# Camera_Board.net
KiCad netlist of a schematic drawn in Altium Designer
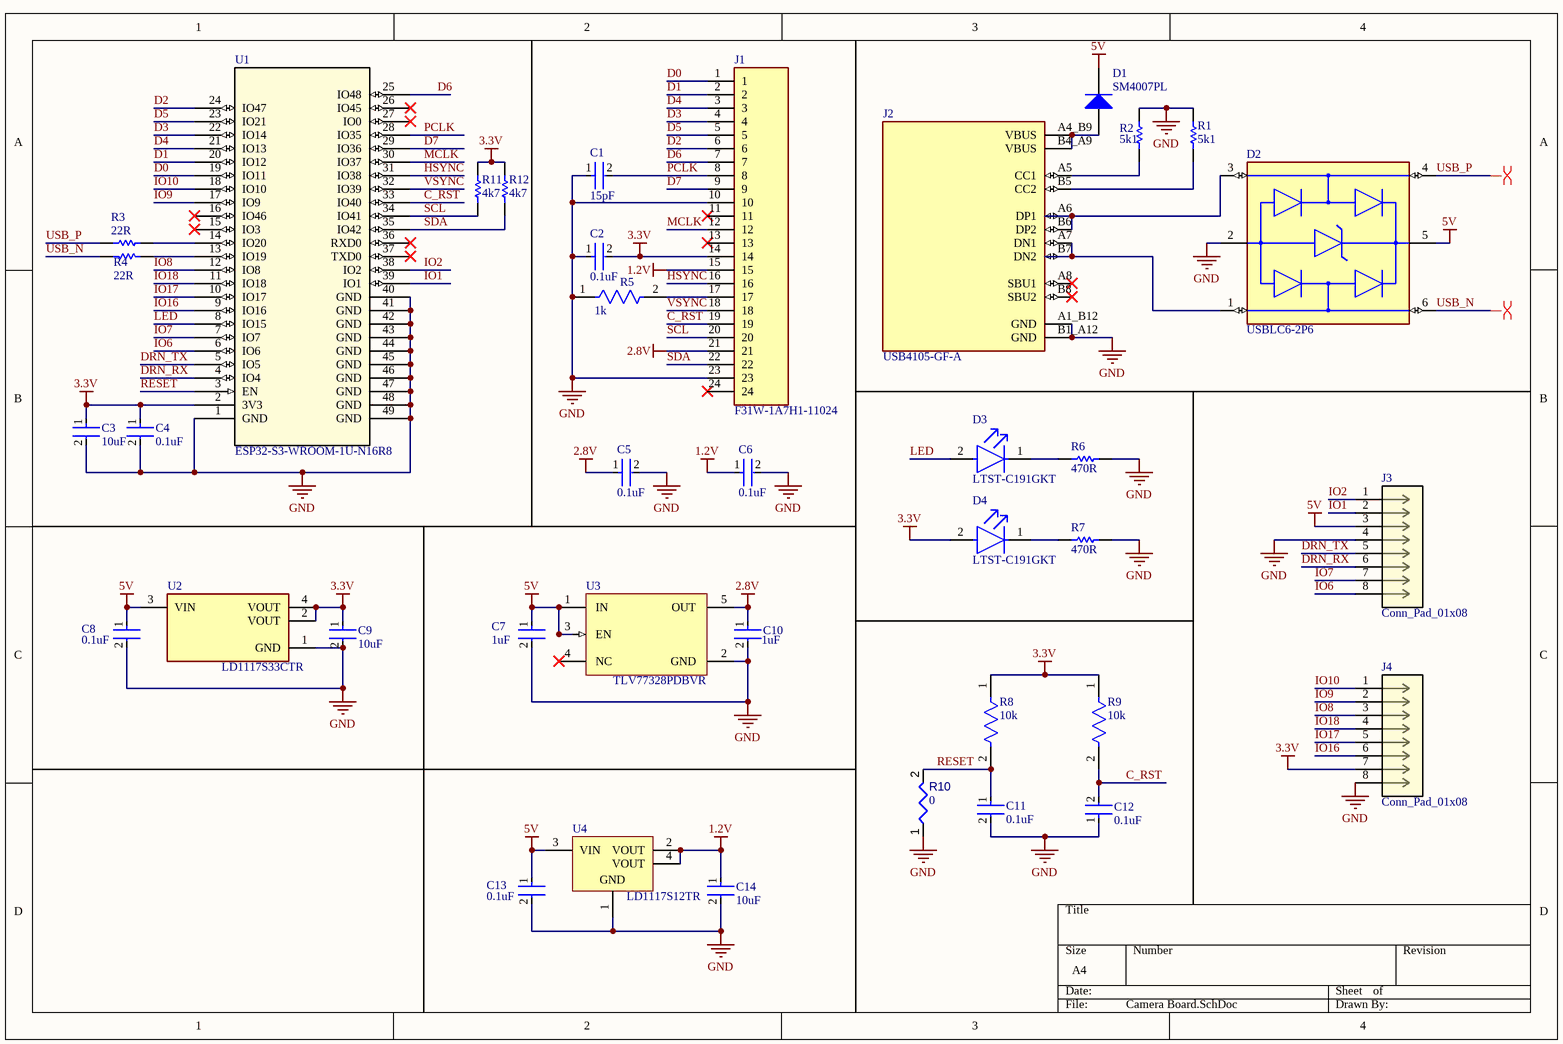
[diagram p0: Camera Board.SchDoc]

(export (version "E")
  (design (tool "Eeschema 10.0.6"))
  (components
    (comp (ref "C1")
      (value "15pF")
      (footprint "FP-CC0402-0_55-IPC_B")
      (description "CAP CER 15PF 50V C0G/NPO 0402")
      (fields (field (name "VOLTAGE") "50V") (field (name "TOLERANCE") "5%"))
      (libsource (lib "Altium Content Vault") (part "b4654b650e69147ec39a6b967a45e02"))
    )
    (comp (ref "C2")
      (value "0.1uF")
      (footprint "FP-GRM155-0_05-IPC_B")
      (description "Chip Multilayer Ceramic Capacitors for General Purpose, 0402, 0.10uF, X7R, 15%, 10%, 50V")
      (fields (field (name "VOLTAGE") "50V") (field (name "TOLERANCE") "10%"))
      (libsource (lib "Altium Content Vault") (part "02cd4be3c70576c341d710602a673aa"))
    )
    (comp (ref "C3")
      (value "10uF")
      (footprint "FP-GRM18-0_15-MFG")
      (description "CAP CER 10UF 10V X5R 0603")
      (fields
        (field (name "OCTOPART") "https://octopart.com/grm188r61a106ke69d-murata-22851381")
        (field (name "MANUFACTURER PART NUMBER") "GRM188R61A106KE69D")
      )
      (libsource (lib "Altium Content Vault") (part "11868f565c42a9108669ba33697ecf6"))
    )
    (comp (ref "C4")
      (value "0.1uF")
      (footprint "FP-CC0603-DA-MFG")
      (description "CAP CER 0.1UF 50V X7R 0603")
      (fields (field (name "MANUFACTURER") "YAGEO") (field (name "VOLTAGE") "50 V"))
      (libsource (lib "Altium Content Vault") (part "11868f565c42a9108669ba33697ecf6"))
    )
    (comp (ref "C5")
      (value "0.1uF")
      (footprint "FP-GRM155-0_05-IPC_B")
      (description "Chip Multilayer Ceramic Capacitors for General Purpose, 0402, 0.10uF, X7R, 15%, 10%, 50V")
      (fields (field (name "VOLTAGE") "50V") (field (name "TOLERANCE") "10%"))
      (libsource (lib "Altium Content Vault") (part "02cd4be3c70576c341d710602a673aa"))
    )
    (comp (ref "C6")
      (value "0.1uF")
      (footprint "FP-GRM155-0_05-IPC_B")
      (description "Chip Multilayer Ceramic Capacitors for General Purpose, 0402, 0.10uF, X7R, 15%, 10%, 50V")
      (fields (field (name "VOLTAGE") "50V") (field (name "TOLERANCE") "10%"))
      (libsource (lib "Altium Content Vault") (part "02cd4be3c70576c341d710602a673aa"))
    )
    (comp (ref "C7")
      (value "1uF")
      (footprint "FP-CC0603-DB-MFG")
      (description "CAP CER 1UF 50V X7R 0603")
      (fields (field (name "TOLERANCE") "10%"))
      (libsource (lib "Altium Content Vault") (part "11868f565c42a9108669ba33697ecf6"))
    )
    (comp (ref "C8")
      (value "0.1uF")
      (footprint "FP-CC0603-DA-MFG")
      (description "CAP CER 0.1UF 50V X7R 0603")
      (fields (field (name "MANUFACTURER") "YAGEO") (field (name "VOLTAGE") "50 V"))
      (libsource (lib "Altium Content Vault") (part "11868f565c42a9108669ba33697ecf6"))
    )
    (comp (ref "C9")
      (value "10uF")
      (footprint "FP-GRM18-0_15-MFG")
      (description "CAP CER 10UF 10V X5R 0603")
      (fields
        (field (name "OCTOPART") "https://octopart.com/grm188r61a106ke69d-murata-22851381")
        (field (name "MANUFACTURER PART NUMBER") "GRM188R61A106KE69D")
      )
      (libsource (lib "Altium Content Vault") (part "11868f565c42a9108669ba33697ecf6"))
    )
    (comp (ref "C10")
      (value "1uF")
      (footprint "FP-CC0603-DB-MFG")
      (description "CAP CER 1UF 50V X7R 0603")
      (fields (field (name "TOLERANCE") "10%"))
      (libsource (lib "Altium Content Vault") (part "11868f565c42a9108669ba33697ecf6"))
    )
    (comp (ref "C11")
      (value "0.1uF")
      (footprint "FP-CC0603-DA-MFG")
      (description "CAP CER 0.1UF 50V X7R 0603")
      (fields (field (name "MANUFACTURER") "YAGEO") (field (name "VOLTAGE") "50 V"))
      (libsource (lib "Altium Content Vault") (part "11868f565c42a9108669ba33697ecf6"))
    )
    (comp (ref "C12")
      (value "0.1uF")
      (footprint "FP-GRM155-0_05-IPC_B")
      (description "Chip Multilayer Ceramic Capacitors for General Purpose, 0402, 0.10uF, X7R, 15%, 10%, 50V")
      (fields (field (name "VOLTAGE") "50V") (field (name "TOLERANCE") "10%"))
      (libsource (lib "Altium Content Vault") (part "02cd4be3c70576c341d710602a673aa"))
    )
    (comp (ref "C13")
      (value "0.1uF")
      (footprint "FP-CC0603-DA-MFG")
      (description "CAP CER 0.1UF 50V X7R 0603")
      (fields (field (name "MANUFACTURER") "YAGEO") (field (name "VOLTAGE") "50 V"))
      (libsource (lib "Altium Content Vault") (part "11868f565c42a9108669ba33697ecf6"))
    )
    (comp (ref "C14")
      (value "10uF")
      (footprint "FP-GRM18-0_15-MFG")
      (description "CAP CER 10UF 10V X5R 0603")
      (fields
        (field (name "OCTOPART") "https://octopart.com/grm188r61a106ke69d-murata-22851381")
        (field (name "MANUFACTURER PART NUMBER") "GRM188R61A106KE69D")
      )
      (libsource (lib "Altium Content Vault") (part "11868f565c42a9108669ba33697ecf6"))
    )
    (comp (ref "D1")
      (value "SM4007PL")
      (footprint "MCC-SOD-123FL_V")
      (description "Silion Rectifier, 1 A, 1000 V, -65 to 175 degC, 2-Pin SMD, RoHS, Tape and Reel")
      (fields (field (name "MANUFACTURER") "Micro Commercial Components"))
      (libsource (lib "Altium Content Vault") (part "D-AK-2"))
    )
    (comp (ref "D2")
      (value "USBLC6-2P6")
      (footprint "FP-SOT-666-MFG")
      (description "TVS DIODE 5.25V 17V SOT666")
      (libsource (lib "Altium Content Vault") (part "c871e55f7e3243d341edbd671b98d92"))
    )
    (comp (ref "D3")
      (value "LTST-C191GKT")
      (footprint "FP-LTST-C191GKT-MFG")
      (description "LED GREEN CLEAR CHIP SMD")
      (libsource (lib "Altium Content Vault") (part "8706943c75ba83719d021d2fdc84c58"))
    )
    (comp (ref "D4")
      (value "LTST-C191GKT")
      (footprint "FP-LTST-C191GKT-MFG")
      (description "LED GREEN CLEAR CHIP SMD")
      (libsource (lib "Altium Content Vault") (part "8706943c75ba83719d021d2fdc84c58"))
    )
    (comp (ref "J1")
      (value "F31W-1A7H1-11024")
      (footprint "AMPHENOL_F31W-1A7H1-11024")
      (fields (field (name "MF") "Amphenol ICC / Aorora"))
      (libsource (lib "Adam Turaj") (part "F31W-1A7H1-11024"))
    )
    (comp (ref "J2")
      (value "USB4105-GF-A")
      (footprint "GCT_USB4105-GF-A")
      (fields (field (name "MF") "{'manufacturer': u'GCT'}"))
      (libsource (lib "Adam Turaj") (part "USB4105-GF-A"))
    )
    (comp (ref "J3")
      (value "Conn_Pad_01x08")
      (footprint "CONN_SM08B-GHS-TB_JST")
      (description "Description")
      (fields (field (name "COPYRIGHT") "Copyright (C) 2026 Ultra Librarian. All rights reserved."))
      (libsource (lib "Adam Turaj") (part "SM08B-GHS-TB"))
    )
    (comp (ref "J4")
      (value "Conn_Pad_01x08")
      (footprint "CONN_SM08B-GHS-TB_JST")
      (description "Description")
      (fields (field (name "COPYRIGHT") "Copyright (C) 2026 Ultra Librarian. All rights reserved."))
      (libsource (lib "Adam Turaj") (part "SM08B-GHS-TB"))
    )
    (comp (ref "R1")
      (value "5k1")
      (footprint "RESC1608X55X25ML10T15")
      (fields (field (name "MANUFACTURER") "Yageo") (field (name "PART NUMBER") "RC0603FR-075K1L"))
      (libsource (lib "Altium Content Vault") (part "RES"))
    )
    (comp (ref "R2")
      (value "5k1")
      (footprint "RESC1608X55X25ML10T15")
      (fields (field (name "MANUFACTURER") "Yageo") (field (name "PART NUMBER") "RC0603FR-075K1L"))
      (libsource (lib "Altium Content Vault") (part "RES"))
    )
    (comp (ref "R3")
      (value "22R")
      (footprint "RESC1608X55X25NL10T15")
      (description "Chip Resistor, 22 Ohm, +/- 1%, 0.1 W, -55 to 155 degC, 0603 (1608 Metric), RoHS, Tape and Reel")
      (libsource (lib "Altium Content Vault") (part "RES-2"))
    )
    (comp (ref "R4")
      (value "22R")
      (footprint "RESC1608X55X25NL10T15")
      (description "Chip Resistor, 22 Ohm, +/- 1%, 0.1 W, -55 to 155 degC, 0603 (1608 Metric), RoHS, Tape and Reel")
      (libsource (lib "Altium Content Vault") (part "RES-2"))
    )
    (comp (ref "R5")
      (value "1k")
      (footprint "FP-RC0603-0_55-IPC_C")
      (description "RES 1K OHM 1% 1/10W 0603")
      (fields (field (name "TOLERANCE") "1%"))
      (libsource (lib "Altium Content Vault") (part "1029c3af85768c4190bb7ad29bc67b5"))
    )
    (comp (ref "R6")
      (value "470R")
      (footprint "RESC1608X55X25LL10T15")
      (libsource (lib "Altium Content Vault") (part "RES-2"))
    )
    (comp (ref "R7")
      (value "470R")
      (footprint "RESC1608X55X25LL10T15")
      (libsource (lib "Altium Content Vault") (part "RES-2"))
    )
    (comp (ref "R8")
      (value "10k")
      (footprint "FP-RC0603-0_55-IPC_C")
      (description "RES 10K OHM 1% 1/10W 0603")
      (fields (field (name "TOLERANCE") "1%"))
      (libsource (lib "Altium Content Vault") (part "1029c3af85768c4190bb7ad29bc67b5"))
    )
    (comp (ref "R9")
      (value "10k")
      (footprint "FP-RC0603-0_55-IPC_C")
      (description "RES 10K OHM 1% 1/10W 0603")
      (fields (field (name "TOLERANCE") "1%"))
      (libsource (lib "Altium Content Vault") (part "1029c3af85768c4190bb7ad29bc67b5"))
    )
    (comp (ref "R10")
      (value "0")
      (footprint "RESC0603(1608)_L")
      (description "Jumper 0603")
      (libsource (lib "UWFE_2025_designs") (part "RES-2"))
    )
    (comp (ref "R11")
      (value "4k7")
      (footprint "RESC1608X55X25LL10T15")
      (description "Chip Resistor, 4.7 KOhm, +/- 1%, 0.1 W, -55 to 155 degC, 0603 (1608 Metric), RoHS, Tape and Reel")
      (fields (field (name "MANUFACTURER") "Yageo") (field (name "TOLERANCE") "1%"))
      (libsource (lib "Altium Content Vault") (part "RES-2"))
    )
    (comp (ref "R12")
      (value "4k7")
      (footprint "RESC1608X55X25LL10T15")
      (description "Chip Resistor, 4.7 KOhm, +/- 1%, 0.1 W, -55 to 155 degC, 0603 (1608 Metric), RoHS, Tape and Reel")
      (fields (field (name "MANUFACTURER") "Yageo") (field (name "TOLERANCE") "1%"))
      (libsource (lib "Altium Content Vault") (part "RES-2"))
    )
    (comp (ref "U1")
      (value "ESP32-S3-WROOM-1U-N16R8")
      (footprint "ESP32-S3-WROOM-1U_EXP")
      (description "Description")
      (fields (field (name "COPYRIGHT") "Copyright (C) 2025 Ultra Librarian. All rights reserved."))
      (libsource (lib "UWFE_2025_designs") (part "ESP32-S3-WROOM-1U-N16R8"))
    )
    (comp (ref "U2")
      (value "LD1117S33CTR")
      (footprint "FP-SOT-223-0046067_14-MFG")
      (description "IC REG LINEAR 3.3V 800MA SOT223")
      (libsource (lib "Altium Content Vault") (part "7818869c5c16ceab15634627166a29d"))
    )
    (comp (ref "U3")
      (value "TLV77328PDBVR")
      (footprint "DBV0005A_MFG")
      (description "300-mA high-PSRR low-IQ low-dropout regulator with enable 5-SOT-23 -40 to 85")
      (libsource (lib "Altium Content Vault") (part "e913c5229f21c84fcd86506975bf48d"))
    )
    (comp (ref "U4")
      (value "LD1117S12TR")
      (footprint "SOT-223_M")
      (description "Fixed Low Drop Positive Voltage Regulator, 1.2V, 4-Pin SOT-223, Tape and Reel")
      (libsource (lib "Altium Content Vault") (part "PM-REG-LD1117-SOT4"))
    )
  )
  (nets
    (net (code "1") (name "/C_RST") (class "Default")
      (node (ref "C12") (pin "2") (pinfunction "2_2") (pintype "passive"))
      (node (ref "J1") (pin "19") (pinfunction "19_19") (pintype "passive"))
      (node (ref "R9") (pin "2") (pinfunction "2_2") (pintype "passive"))
      (node (ref "U1") (pin "33") (pinfunction "IO40_33") (pintype "bidirectional"))
    )
    (net (code "2") (name "/D0") (class "Default")
      (node (ref "J1") (pin "1") (pinfunction "1_1") (pintype "passive"))
      (node (ref "U1") (pin "19") (pinfunction "IO11_19") (pintype "bidirectional"))
    )
    (net (code "3") (name "/D1") (class "Default")
      (node (ref "J1") (pin "2") (pinfunction "2_2") (pintype "passive"))
      (node (ref "U1") (pin "20") (pinfunction "IO12_20") (pintype "bidirectional"))
    )
    (net (code "4") (name "/D2") (class "Default")
      (node (ref "J1") (pin "6") (pinfunction "6_6") (pintype "passive"))
      (node (ref "U1") (pin "24") (pinfunction "IO47_24") (pintype "bidirectional"))
    )
    (net (code "5") (name "/D3") (class "Default")
      (node (ref "J1") (pin "4") (pinfunction "4_4") (pintype "passive"))
      (node (ref "U1") (pin "22") (pinfunction "IO14_22") (pintype "bidirectional"))
    )
    (net (code "6") (name "/D4") (class "Default")
      (node (ref "J1") (pin "3") (pinfunction "3_3") (pintype "passive"))
      (node (ref "U1") (pin "21") (pinfunction "IO13_21") (pintype "bidirectional"))
    )
    (net (code "7") (name "/D5") (class "Default")
      (node (ref "J1") (pin "5") (pinfunction "5_5") (pintype "passive"))
      (node (ref "U1") (pin "23") (pinfunction "IO21_23") (pintype "bidirectional"))
    )
    (net (code "8") (name "/D6") (class "Default")
      (node (ref "J1") (pin "7") (pinfunction "7_7") (pintype "passive"))
      (node (ref "U1") (pin "25") (pinfunction "IO48_25") (pintype "bidirectional"))
    )
    (net (code "9") (name "/D7") (class "Default")
      (node (ref "J1") (pin "9") (pinfunction "9_9") (pintype "passive"))
      (node (ref "U1") (pin "29") (pinfunction "IO36_29") (pintype "bidirectional"))
    )
    (net (code "10") (name "/DRN_RX") (class "Default")
      (node (ref "J3") (pin "6") (pinfunction "6_6") (pintype "passive"))
      (node (ref "U1") (pin "4") (pinfunction "IO4_4") (pintype "bidirectional"))
    )
    (net (code "11") (name "/DRN_TX") (class "Default")
      (node (ref "J3") (pin "5") (pinfunction "5_5") (pintype "passive"))
      (node (ref "U1") (pin "5") (pinfunction "IO5_5") (pintype "bidirectional"))
    )
    (net (code "12") (name "/HSYNC") (class "Default")
      (node (ref "J1") (pin "16") (pinfunction "16_16") (pintype "passive"))
      (node (ref "U1") (pin "31") (pinfunction "IO38_31") (pintype "bidirectional"))
    )
    (net (code "13") (name "/IO1") (class "Default")
      (node (ref "J3") (pin "2") (pinfunction "2_2") (pintype "passive"))
      (node (ref "U1") (pin "39") (pinfunction "IO1_39") (pintype "bidirectional"))
    )
    (net (code "14") (name "/IO2") (class "Default")
      (node (ref "J3") (pin "1") (pinfunction "1_1") (pintype "passive"))
      (node (ref "U1") (pin "38") (pinfunction "IO2_38") (pintype "bidirectional"))
    )
    (net (code "15") (name "/IO6") (class "Default")
      (node (ref "J3") (pin "8") (pinfunction "8_8") (pintype "passive"))
      (node (ref "U1") (pin "6") (pinfunction "IO6_6") (pintype "bidirectional"))
    )
    (net (code "16") (name "/IO7") (class "Default")
      (node (ref "J3") (pin "7") (pinfunction "7_7") (pintype "passive"))
      (node (ref "U1") (pin "7") (pinfunction "IO7_7") (pintype "bidirectional"))
    )
    (net (code "17") (name "/IO8") (class "Default")
      (node (ref "J4") (pin "3") (pinfunction "3_3") (pintype "passive"))
      (node (ref "U1") (pin "12") (pinfunction "IO8_12") (pintype "bidirectional"))
    )
    (net (code "18") (name "/IO9") (class "Default")
      (node (ref "J4") (pin "2") (pinfunction "2_2") (pintype "passive"))
      (node (ref "U1") (pin "17") (pinfunction "IO9_17") (pintype "bidirectional"))
    )
    (net (code "19") (name "/IO10") (class "Default")
      (node (ref "J4") (pin "1") (pinfunction "1_1") (pintype "passive"))
      (node (ref "U1") (pin "18") (pinfunction "IO10_18") (pintype "bidirectional"))
    )
    (net (code "20") (name "/IO16") (class "Default")
      (node (ref "J4") (pin "6") (pinfunction "6_6") (pintype "passive"))
      (node (ref "U1") (pin "9") (pinfunction "IO16_9") (pintype "bidirectional"))
    )
    (net (code "21") (name "/IO17") (class "Default")
      (node (ref "J4") (pin "5") (pinfunction "5_5") (pintype "passive"))
      (node (ref "U1") (pin "10") (pinfunction "IO17_10") (pintype "bidirectional"))
    )
    (net (code "22") (name "/IO18") (class "Default")
      (node (ref "J4") (pin "4") (pinfunction "4_4") (pintype "passive"))
      (node (ref "U1") (pin "11") (pinfunction "IO18_11") (pintype "bidirectional"))
    )
    (net (code "23") (name "/LED") (class "Default")
      (node (ref "D3") (pin "2") (pinfunction "A_2") (pintype "passive"))
      (node (ref "U1") (pin "8") (pinfunction "IO15_8") (pintype "bidirectional"))
    )
    (net (code "24") (name "/MCLK") (class "Default")
      (node (ref "J1") (pin "12") (pinfunction "12_12") (pintype "passive"))
      (node (ref "U1") (pin "30") (pinfunction "IO37_30") (pintype "bidirectional"))
    )
    (net (code "25") (name "/PCLK") (class "Default")
      (node (ref "C1") (pin "2") (pinfunction "2_2") (pintype "passive"))
      (node (ref "J1") (pin "8") (pinfunction "8_8") (pintype "passive"))
      (node (ref "U1") (pin "28") (pinfunction "IO35_28") (pintype "bidirectional"))
    )
    (net (code "26") (name "/RESET") (class "Default")
      (node (ref "C11") (pin "1") (pinfunction "1_1") (pintype "passive"))
      (node (ref "R10") (pin "2") (pinfunction "2_2") (pintype "passive"))
      (node (ref "R8") (pin "2") (pinfunction "2_2") (pintype "passive"))
      (node (ref "U1") (pin "3") (pinfunction "EN_3") (pintype "input"))
    )
    (net (code "27") (name "/SCL") (class "Default")
      (node (ref "J1") (pin "20") (pinfunction "20_20") (pintype "passive"))
      (node (ref "R11") (pin "1") (pinfunction "1_1") (pintype "passive"))
      (node (ref "U1") (pin "34") (pinfunction "IO41_34") (pintype "bidirectional"))
    )
    (net (code "28") (name "/SDA") (class "Default")
      (node (ref "J1") (pin "22") (pinfunction "22_22") (pintype "passive"))
      (node (ref "R12") (pin "1") (pinfunction "1_1") (pintype "passive"))
      (node (ref "U1") (pin "35") (pinfunction "IO42_35") (pintype "bidirectional"))
    )
    (net (code "29") (name "/USB_N") (class "Default")
      (node (ref "D2") (pin "6") (pinfunction "I/O1_6") (pintype "bidirectional"))
      (node (ref "R4") (pin "1") (pinfunction "1_1") (pintype "passive"))
    )
    (net (code "30") (name "/USB_P") (class "Default")
      (node (ref "D2") (pin "4") (pinfunction "I/O2_4") (pintype "bidirectional"))
      (node (ref "R3") (pin "1") (pinfunction "1_1") (pintype "passive"))
    )
    (net (code "31") (name "/VSYNC") (class "Default")
      (node (ref "J1") (pin "18") (pinfunction "18_18") (pintype "passive"))
      (node (ref "U1") (pin "32") (pinfunction "IO39_32") (pintype "bidirectional"))
    )
    (net (code "32") (name "1.2V") (class "Default")
      (node (ref "C14") (pin "1") (pinfunction "1_1") (pintype "passive"))
      (node (ref "C6") (pin "1") (pinfunction "1_1") (pintype "passive"))
      (node (ref "J1") (pin "15") (pinfunction "15_15") (pintype "passive"))
      (node (ref "U4") (pin "2") (pinfunction "VOUT_2") (pintype "power_in"))
      (node (ref "U4") (pin "4") (pinfunction "VOUT_4") (pintype "power_in"))
    )
    (net (code "33") (name "2.8V") (class "Default")
      (node (ref "C10") (pin "1") (pinfunction "1_1") (pintype "passive"))
      (node (ref "C5") (pin "1") (pinfunction "1_1") (pintype "passive"))
      (node (ref "J1") (pin "21") (pinfunction "21_21") (pintype "passive"))
      (node (ref "U3") (pin "5") (pinfunction "OUT_5") (pintype "passive"))
    )
    (net (code "34") (name "3.3V") (class "Default")
      (node (ref "C2") (pin "2") (pinfunction "2_2") (pintype "passive"))
      (node (ref "C3") (pin "1") (pinfunction "1_1") (pintype "passive"))
      (node (ref "C4") (pin "1") (pinfunction "1_1") (pintype "passive"))
      (node (ref "C9") (pin "1") (pinfunction "1_1") (pintype "passive"))
      (node (ref "D4") (pin "2") (pinfunction "A_2") (pintype "passive"))
      (node (ref "J1") (pin "14") (pinfunction "14_14") (pintype "passive"))
      (node (ref "J4") (pin "7") (pinfunction "7_7") (pintype "passive"))
      (node (ref "R11") (pin "2") (pinfunction "2_2") (pintype "passive"))
      (node (ref "R12") (pin "2") (pinfunction "2_2") (pintype "passive"))
      (node (ref "R8") (pin "1") (pinfunction "1_1") (pintype "passive"))
      (node (ref "R9") (pin "1") (pinfunction "1_1") (pintype "passive"))
      (node (ref "U1") (pin "2") (pinfunction "3V3_2") (pintype "power_in"))
      (node (ref "U2") (pin "2") (pinfunction "VOUT_2") (pintype "power_in"))
      (node (ref "U2") (pin "4") (pinfunction "VOUT_4") (pintype "power_in"))
    )
    (net (code "35") (name "5V") (class "Default")
      (node (ref "C13") (pin "1") (pinfunction "1_1") (pintype "passive"))
      (node (ref "C7") (pin "1") (pinfunction "1_1") (pintype "passive"))
      (node (ref "C8") (pin "1") (pinfunction "1_1") (pintype "passive"))
      (node (ref "D1") (pin "2") (pinfunction "K_2") (pintype "passive"))
      (node (ref "D2") (pin "5") (pinfunction "VBUS_5") (pintype "power_in"))
      (node (ref "J3") (pin "3") (pinfunction "3_3") (pintype "passive"))
      (node (ref "U2") (pin "3") (pinfunction "VIN_3") (pintype "power_in"))
      (node (ref "U3") (pin "1") (pinfunction "IN_1") (pintype "power_in"))
      (node (ref "U3") (pin "3") (pinfunction "EN_3") (pintype "input"))
      (node (ref "U4") (pin "3") (pinfunction "VIN_3") (pintype "power_in"))
    )
    (net (code "36") (name "GND") (class "Default")
      (node (ref "C1") (pin "1") (pinfunction "1_1") (pintype "passive"))
      (node (ref "C10") (pin "2") (pinfunction "2_2") (pintype "passive"))
      (node (ref "C11") (pin "2") (pinfunction "2_2") (pintype "passive"))
      (node (ref "C12") (pin "1") (pinfunction "1_1") (pintype "passive"))
      (node (ref "C13") (pin "2") (pinfunction "2_2") (pintype "passive"))
      (node (ref "C14") (pin "2") (pinfunction "2_2") (pintype "passive"))
      (node (ref "C2") (pin "1") (pinfunction "1_1") (pintype "passive"))
      (node (ref "C3") (pin "2") (pinfunction "2_2") (pintype "passive"))
      (node (ref "C4") (pin "2") (pinfunction "2_2") (pintype "passive"))
      (node (ref "C5") (pin "2") (pinfunction "2_2") (pintype "passive"))
      (node (ref "C6") (pin "2") (pinfunction "2_2") (pintype "passive"))
      (node (ref "C7") (pin "2") (pinfunction "2_2") (pintype "passive"))
      (node (ref "C8") (pin "2") (pinfunction "2_2") (pintype "passive"))
      (node (ref "C9") (pin "2") (pinfunction "2_2") (pintype "passive"))
      (node (ref "D2") (pin "2") (pinfunction "GND_2") (pintype "power_in"))
      (node (ref "J1") (pin "10") (pinfunction "10_10") (pintype "passive"))
      (node (ref "J1") (pin "23") (pinfunction "23_23") (pintype "passive"))
      (node (ref "J2") (pin "A1_B12") (pinfunction "GND_A1_B12") (pintype "power_in"))
      (node (ref "J2") (pin "B1_A12") (pinfunction "GND_B1_A12") (pintype "power_in"))
      (node (ref "J3") (pin "4") (pinfunction "4_4") (pintype "passive"))
      (node (ref "J4") (pin "8") (pinfunction "8_8") (pintype "passive"))
      (node (ref "R1") (pin "2") (pinfunction "2_2") (pintype "passive"))
      (node (ref "R10") (pin "1") (pinfunction "1_1") (pintype "passive"))
      (node (ref "R2") (pin "2") (pinfunction "2_2") (pintype "passive"))
      (node (ref "R5") (pin "1") (pinfunction "1_1") (pintype "passive"))
      (node (ref "R6") (pin "2") (pinfunction "2_2") (pintype "passive"))
      (node (ref "R7") (pin "2") (pinfunction "2_2") (pintype "passive"))
      (node (ref "U1") (pin "1") (pinfunction "GND_1") (pintype "power_in"))
      (node (ref "U1") (pin "40") (pinfunction "GND_40") (pintype "power_in"))
      (node (ref "U1") (pin "41") (pinfunction "GND_41") (pintype "power_in"))
      (node (ref "U1") (pin "42") (pinfunction "GND_42") (pintype "power_in"))
      (node (ref "U1") (pin "43") (pinfunction "GND_43") (pintype "power_in"))
      (node (ref "U1") (pin "44") (pinfunction "GND_44") (pintype "power_in"))
      (node (ref "U1") (pin "45") (pinfunction "GND_45") (pintype "power_in"))
      (node (ref "U1") (pin "46") (pinfunction "GND_46") (pintype "power_in"))
      (node (ref "U1") (pin "47") (pinfunction "GND_47") (pintype "power_in"))
      (node (ref "U1") (pin "48") (pinfunction "GND_48") (pintype "power_in"))
      (node (ref "U1") (pin "49") (pinfunction "GND_49") (pintype "power_in"))
      (node (ref "U2") (pin "1") (pinfunction "GND_1") (pintype "power_in"))
      (node (ref "U3") (pin "2") (pinfunction "GND_2") (pintype "power_in"))
      (node (ref "U4") (pin "1") (pinfunction "GND_1") (pintype "power_in"))
    )
    (net (code "37") (name "Net-(D1-A)") (class "Default")
      (node (ref "D1") (pin "1") (pinfunction "A_1") (pintype "passive"))
      (node (ref "J2") (pin "A4_B9") (pinfunction "VBUS_A4_B9") (pintype "power_in"))
      (node (ref "J2") (pin "B4_A9") (pinfunction "VBUS_B4_A9") (pintype "power_in"))
    )
    (net (code "38") (name "Net-(D3-C)") (class "Default")
      (node (ref "D3") (pin "1") (pinfunction "C_1") (pintype "passive"))
      (node (ref "R6") (pin "1") (pinfunction "1_1") (pintype "passive"))
    )
    (net (code "39") (name "Net-(D4-C)") (class "Default")
      (node (ref "D4") (pin "1") (pinfunction "C_1") (pintype "passive"))
      (node (ref "R7") (pin "1") (pinfunction "1_1") (pintype "passive"))
    )
    (net (code "40") (name "Net-(J1-Pad17)") (class "Default")
      (node (ref "J1") (pin "17") (pinfunction "17_17") (pintype "passive"))
      (node (ref "R5") (pin "2") (pinfunction "2_2") (pintype "passive"))
    )
    (net (code "41") (name "Net-(J2-CC1)") (class "Default")
      (node (ref "J2") (pin "A5") (pinfunction "CC1_A5") (pintype "bidirectional"))
      (node (ref "R2") (pin "1") (pinfunction "1_1") (pintype "passive"))
    )
    (net (code "42") (name "Net-(J2-CC2)") (class "Default")
      (node (ref "J2") (pin "B5") (pinfunction "CC2_B5") (pintype "bidirectional"))
      (node (ref "R1") (pin "1") (pinfunction "1_1") (pintype "passive"))
    )
    (net (code "43") (name "Net-(J2-DN1)") (class "Default")
      (node (ref "D2") (pin "1") (pinfunction "I/O1_1") (pintype "bidirectional"))
      (node (ref "J2") (pin "A7") (pinfunction "DN1_A7") (pintype "bidirectional"))
      (node (ref "J2") (pin "B7") (pinfunction "DN2_B7") (pintype "bidirectional"))
    )
    (net (code "44") (name "Net-(J2-DP1)") (class "Default")
      (node (ref "D2") (pin "3") (pinfunction "I/O2_3") (pintype "bidirectional"))
      (node (ref "J2") (pin "A6") (pinfunction "DP1_A6") (pintype "bidirectional"))
      (node (ref "J2") (pin "B6") (pinfunction "DP2_B6") (pintype "bidirectional"))
    )
    (net (code "45") (name "Net-(U1-IO19)") (class "Default")
      (node (ref "R4") (pin "2") (pinfunction "2_2") (pintype "passive"))
      (node (ref "U1") (pin "13") (pinfunction "IO19_13") (pintype "bidirectional"))
    )
    (net (code "46") (name "Net-(U1-IO20)") (class "Default")
      (node (ref "R3") (pin "2") (pinfunction "2_2") (pintype "passive"))
      (node (ref "U1") (pin "14") (pinfunction "IO20_14") (pintype "bidirectional"))
    )
    (net (code "47") (name "unconnected-(J1-Pad11)") (class "Default")
      (node (ref "J1") (pin "11") (pinfunction "11_11") (pintype "passive+no_connect"))
    )
    (net (code "48") (name "unconnected-(J1-Pad13)") (class "Default")
      (node (ref "J1") (pin "13") (pinfunction "13_13") (pintype "passive+no_connect"))
    )
    (net (code "49") (name "unconnected-(J1-Pad24)") (class "Default")
      (node (ref "J1") (pin "24") (pinfunction "24_24") (pintype "passive+no_connect"))
    )
    (net (code "50") (name "unconnected-(J2-SBU1-PadA8)") (class "Default")
      (node (ref "J2") (pin "A8") (pinfunction "SBU1_A8") (pintype "bidirectional+no_connect"))
    )
    (net (code "51") (name "unconnected-(J2-SBU2-PadB8)") (class "Default")
      (node (ref "J2") (pin "B8") (pinfunction "SBU2_B8") (pintype "bidirectional+no_connect"))
    )
    (net (code "52") (name "unconnected-(U1-IO0-Pad27)") (class "Default")
      (node (ref "U1") (pin "27") (pinfunction "IO0_27") (pintype "bidirectional+no_connect"))
    )
    (net (code "53") (name "unconnected-(U1-IO3-Pad15)") (class "Default")
      (node (ref "U1") (pin "15") (pinfunction "IO3_15") (pintype "bidirectional+no_connect"))
    )
    (net (code "54") (name "unconnected-(U1-IO45-Pad26)") (class "Default")
      (node (ref "U1") (pin "26") (pinfunction "IO45_26") (pintype "bidirectional+no_connect"))
    )
    (net (code "55") (name "unconnected-(U1-IO46-Pad16)") (class "Default")
      (node (ref "U1") (pin "16") (pinfunction "IO46_16") (pintype "bidirectional+no_connect"))
    )
    (net (code "56") (name "unconnected-(U1-RXD0-Pad36)") (class "Default")
      (node (ref "U1") (pin "36") (pinfunction "RXD0_36") (pintype "bidirectional+no_connect"))
    )
    (net (code "57") (name "unconnected-(U1-TXD0-Pad37)") (class "Default")
      (node (ref "U1") (pin "37") (pinfunction "TXD0_37") (pintype "bidirectional+no_connect"))
    )
    (net (code "58") (name "unconnected-(U3-NC-Pad4)") (class "Default")
      (node (ref "U3") (pin "4") (pinfunction "NC_4") (pintype "passive+no_connect"))
    )
  )
)
